# USB_Tool.net
KiCad netlist of a schematic drawn in Altium Designer
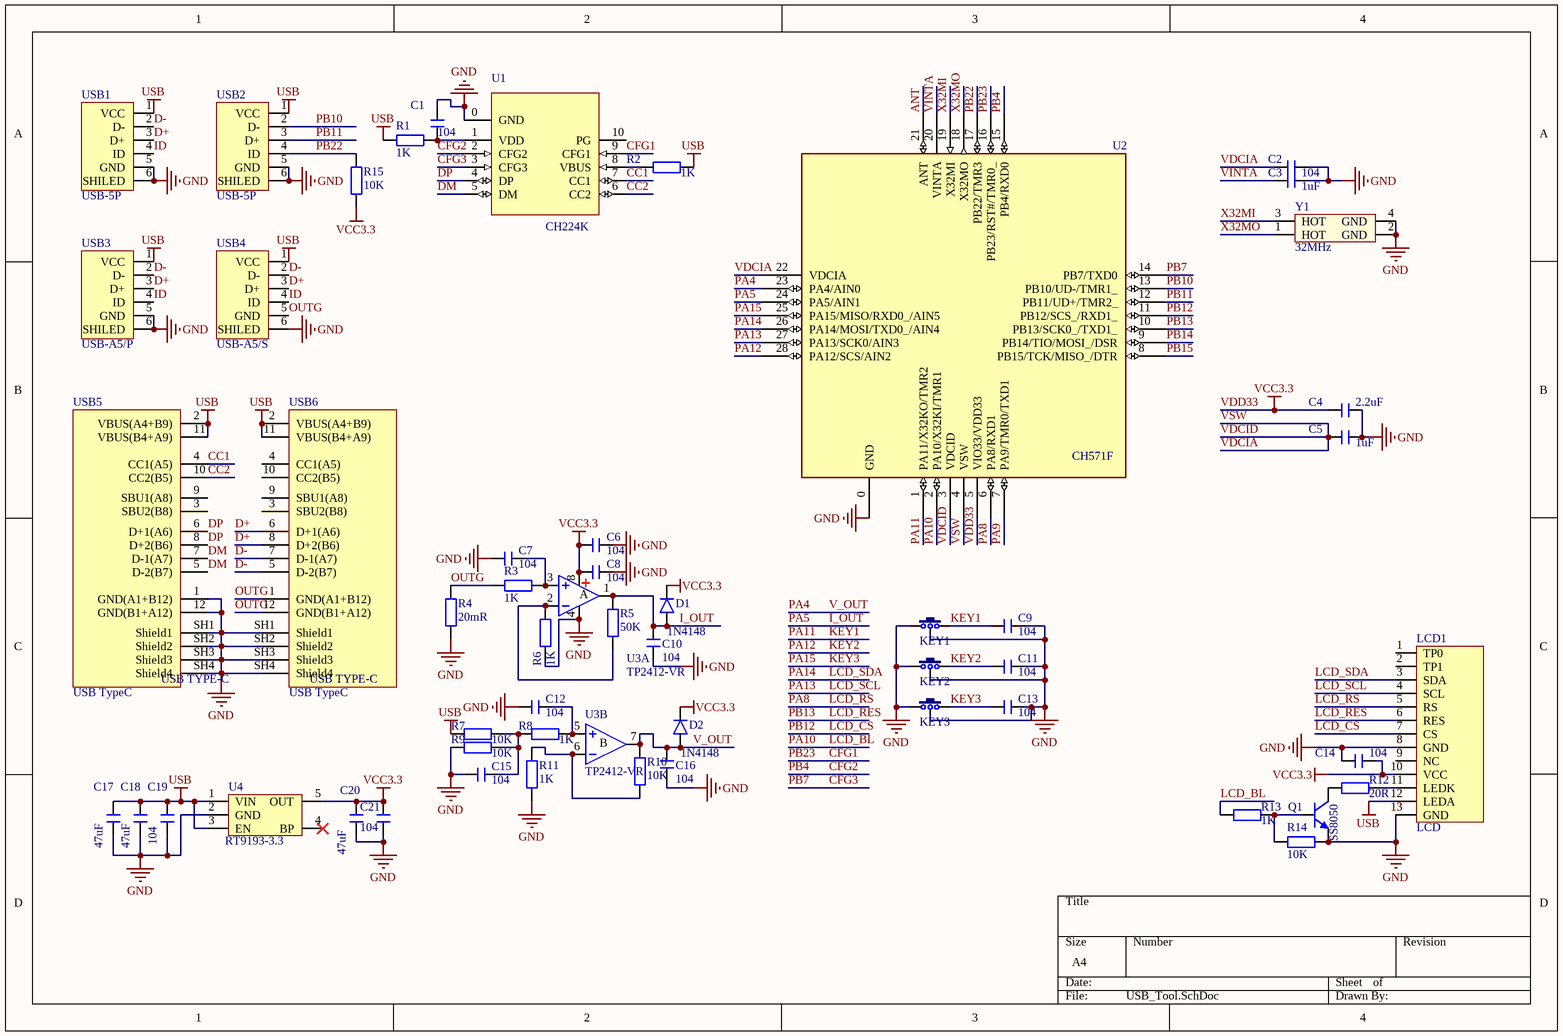
[diagram p0: USB_Tool.SchDoc]

(export (version "E")
  (design (tool "Eeschema 10.0.6"))
  (components
    (comp (ref "C1")
      (value "104")
      (footprint "C 0603_L")
      (description "无极性贴片电容")
      (fields (field (name "版权归属") "正点原子"))
      (libsource (lib "电阻-电容-电感") (part "C"))
    )
    (comp (ref "C2")
      (value "104")
      (footprint "C 0603_L")
      (description "无极性贴片电容")
      (libsource (lib "LovelessingSch") (part "C"))
    )
    (comp (ref "C3")
      (value "1uF")
      (footprint "C 0603_L")
      (description "无极性贴片电容")
      (libsource (lib "LovelessingSch") (part "C"))
    )
    (comp (ref "C4")
      (value "2.2uF")
      (footprint "C 0603_L")
      (description "无极性贴片电容")
      (libsource (lib "LovelessingSch") (part "C"))
    )
    (comp (ref "C5")
      (value "1uF")
      (footprint "C 0603_L")
      (description "无极性贴片电容")
      (libsource (lib "LovelessingSch") (part "C"))
    )
    (comp (ref "C6")
      (value "104")
      (footprint "C 0603_L")
      (description "无极性贴片电容")
      (fields (field (name "版权归属") "正点原子"))
      (libsource (lib "电阻-电容-电感") (part "C"))
    )
    (comp (ref "C7")
      (value "104")
      (footprint "C 0603_L")
      (description "无极性贴片电容")
      (fields (field (name "版权归属") "正点原子"))
      (libsource (lib "电阻-电容-电感") (part "C"))
    )
    (comp (ref "C8")
      (value "104")
      (footprint "C 0603_L")
      (description "无极性贴片电容")
      (fields (field (name "版权归属") "正点原子"))
      (libsource (lib "电阻-电容-电感") (part "C"))
    )
    (comp (ref "C9")
      (value "104")
      (footprint "C 0603_L")
      (description "无极性贴片电容")
      (fields (field (name "版权归属") "正点原子"))
      (libsource (lib "电阻-电容-电感") (part "C"))
    )
    (comp (ref "C10")
      (value "104")
      (footprint "C 0603_L")
      (description "无极性贴片电容")
      (fields (field (name "版权归属") "正点原子"))
      (libsource (lib "电阻-电容-电感") (part "C"))
    )
    (comp (ref "C11")
      (value "104")
      (footprint "C 0603_L")
      (description "无极性贴片电容")
      (fields (field (name "版权归属") "正点原子"))
      (libsource (lib "电阻-电容-电感") (part "C"))
    )
    (comp (ref "C12")
      (value "104")
      (footprint "C 0603_L")
      (description "无极性贴片电容")
      (fields (field (name "版权归属") "正点原子"))
      (libsource (lib "电阻-电容-电感") (part "C"))
    )
    (comp (ref "C13")
      (value "104")
      (footprint "C 0603_L")
      (description "无极性贴片电容")
      (fields (field (name "版权归属") "正点原子"))
      (libsource (lib "电阻-电容-电感") (part "C"))
    )
    (comp (ref "C14")
      (value "104")
      (footprint "C 0603_L")
      (description "无极性电容")
      (fields (field (name "版权归属") "正点原子"))
      (libsource (lib "正点原子封装库V1.0") (part "C"))
    )
    (comp (ref "C15")
      (value "104")
      (footprint "C 0603_L")
      (description "无极性贴片电容")
      (fields (field (name "版权归属") "正点原子"))
      (libsource (lib "电阻-电容-电感") (part "C"))
    )
    (comp (ref "C16")
      (value "104")
      (footprint "C 0603_L")
      (description "无极性贴片电容")
      (fields (field (name "版权归属") "正点原子"))
      (libsource (lib "电阻-电容-电感") (part "C"))
    )
    (comp (ref "C17")
      (value "47uF")
      (footprint "C 0603_L")
      (description "无极性贴片电容")
      (fields (field (name "版权归属") "正点原子"))
      (libsource (lib "电阻-电容-电感") (part "C"))
    )
    (comp (ref "C18")
      (value "47uF")
      (footprint "C 0603_L")
      (description "无极性贴片电容")
      (fields (field (name "版权归属") "正点原子"))
      (libsource (lib "电阻-电容-电感") (part "C"))
    )
    (comp (ref "C19")
      (value "104")
      (footprint "C 0603_L")
      (description "无极性贴片电容")
      (fields (field (name "版权归属") "正点原子"))
      (libsource (lib "电阻-电容-电感") (part "C"))
    )
    (comp (ref "C20")
      (value "47uF")
      (footprint "C 0603_L")
      (description "无极性贴片电容")
      (fields (field (name "版权归属") "正点原子"))
      (libsource (lib "电阻-电容-电感") (part "C"))
    )
    (comp (ref "C21")
      (value "104")
      (footprint "C 0603_L")
      (description "无极性贴片电容")
      (fields (field (name "版权归属") "正点原子"))
      (libsource (lib "电阻-电容-电感") (part "C"))
    )
    (comp (ref "D1")
      (value "1N4148")
      (footprint "SOD-323")
      (description "二极管")
      (libsource (lib "LovelessingSch") (part "D"))
    )
    (comp (ref "D2")
      (value "1N4148")
      (footprint "SOD-323")
      (description "二极管")
      (libsource (lib "LovelessingSch") (part "D"))
    )
    (comp (ref "KEY1")
      (value "KEY_3")
      (footprint "TSW 2*4*3.5-S-W")
      (description "侧按键")
      (fields (field (name "版权归属") "正点原子"))
      (libsource (lib "正点原子封装库V1.0") (part "KEY_3"))
    )
    (comp (ref "KEY2")
      (value "KEY_3")
      (footprint "TSW 2*4*3.5-S-W")
      (description "侧按键")
      (fields (field (name "版权归属") "正点原子"))
      (libsource (lib "正点原子封装库V1.0") (part "KEY_3"))
    )
    (comp (ref "KEY3")
      (value "KEY_3")
      (footprint "TSW 2*4*3.5-S-W")
      (description "侧按键")
      (fields (field (name "版权归属") "正点原子"))
      (libsource (lib "正点原子封装库V1.0") (part "KEY_3"))
    )
    (comp (ref "LCD1")
      (value "LCD")
      (footprint "0.96LCD")
      (description "0.96 LCD 80*160")
      (fields (field (name "版权归属") "正点原子"))
      (libsource (lib "正点原子封装库V1.0") (part "LCD 0.96"))
    )
    (comp (ref "Q1")
      (value "SS8050")
      (footprint "SOT23-3N")
      (description "高频放大-NPN型")
      (fields (field (name "版权归属") "正点原子"))
      (libsource (lib "正点原子封装库V1.0") (part "8050-SMD"))
    )
    (comp (ref "R1")
      (value "1K")
      (footprint "R 0603_L")
      (description "贴片电阻")
      (libsource (lib "LovelessingSch") (part "R"))
    )
    (comp (ref "R2")
      (value "1K")
      (footprint "R 0603_L")
      (description "贴片电阻")
      (libsource (lib "LovelessingSch") (part "R"))
    )
    (comp (ref "R3")
      (value "1K")
      (footprint "R 0603_L")
      (description "贴片电阻")
      (libsource (lib "LovelessingSch") (part "R"))
    )
    (comp (ref "R4")
      (value "20mR")
      (footprint "R 2512_L")
      (description "贴片电阻")
      (libsource (lib "LovelessingSch") (part "R"))
    )
    (comp (ref "R5")
      (value "50K")
      (footprint "R 0603_L")
      (description "贴片电阻")
      (libsource (lib "LovelessingSch") (part "R"))
    )
    (comp (ref "R6")
      (value "1K")
      (footprint "R 0603_L")
      (description "贴片电阻")
      (libsource (lib "LovelessingSch") (part "R"))
    )
    (comp (ref "R7")
      (value "10K")
      (footprint "R 0603_L")
      (description "贴片电阻")
      (libsource (lib "LovelessingSch") (part "R"))
    )
    (comp (ref "R8")
      (value "1K")
      (footprint "R 0603_L")
      (description "贴片电阻")
      (libsource (lib "LovelessingSch") (part "R"))
    )
    (comp (ref "R9")
      (value "10K")
      (footprint "R 0603_L")
      (description "贴片电阻")
      (libsource (lib "LovelessingSch") (part "R"))
    )
    (comp (ref "R10")
      (value "10K")
      (footprint "R 0603_L")
      (description "贴片电阻")
      (libsource (lib "LovelessingSch") (part "R"))
    )
    (comp (ref "R11")
      (value "1K")
      (footprint "R 0603_L")
      (description "贴片电阻")
      (libsource (lib "LovelessingSch") (part "R"))
    )
    (comp (ref "R12")
      (value "20R")
      (footprint "R 0603_L")
      (description "贴片电阻")
      (libsource (lib "LovelessingSch") (part "R"))
    )
    (comp (ref "R13")
      (value "1K")
      (footprint "R 0603_L")
      (description "贴片电阻")
      (libsource (lib "LovelessingSch") (part "R"))
    )
    (comp (ref "R14")
      (value "10K")
      (footprint "R 0603_L")
      (description "贴片电阻")
      (libsource (lib "LovelessingSch") (part "R"))
    )
    (comp (ref "R15")
      (value "10K")
      (footprint "R 0603_L")
      (description "贴片电阻")
      (libsource (lib "LovelessingSch") (part "R"))
    )
    (comp (ref "U1")
      (value "CH224K")
      (footprint "ESSOP10")
      (description "USB PD & Type-C & Fast Charge Power Consumer Controller")
      (libsource (lib "CHXXX") (part "CH224K"))
    )
    (comp (ref "U2")
      (value "CH571F")
      (footprint "QFN28_4X4")
      (description "RISC-V MCU with BLE/USB/ADC/SPI/2*UART")
      (libsource (lib "LovelessingSch") (part "CH571F"))
    )
    (comp (ref "U3")
      (value "TP2412-VR")
      (footprint "SOP8_N")
      (description "低噪双路运放 5.5V 10MHz 1mV")
      (fields (field (name "版权归属") "正点原子"))
      (libsource (lib "正点原子封装库V1.0") (part "TP2412"))
    )
    (comp (ref "U4")
      (value "RT9193-3.3")
      (footprint "SOT23-5L")
      (description "LDO")
      (fields (field (name "版权归属") "正点原子"))
      (libsource (lib "LDO和DCDC") (part "LDO RT9193"))
    )
    (comp (ref "USB1")
      (value "USB-5P")
      (footprint "USB-micro_B")
      (description "micro_USB母座")
      (fields (field (name "版权归属") "正点原子"))
      (libsource (lib "正点原子封装库V1.0") (part "USB 2.0 micro B"))
    )
    (comp (ref "USB2")
      (value "USB-5P")
      (footprint "USB-micro_B")
      (description "micro_USB母座")
      (fields (field (name "版权归属") "正点原子"))
      (libsource (lib "正点原子封装库V1.0") (part "USB 2.0 micro B"))
    )
    (comp (ref "USB3")
      (value "USB-A5/P")
      (footprint "USB_A5/P_B")
      (description "micro_USB母座")
      (fields (field (name "版权归属") "正点原子"))
      (libsource (lib "正点原子封装库V1.0") (part "USB 2.0 micro B"))
    )
    (comp (ref "USB4")
      (value "USB-A5/S")
      (footprint "USB_A5/S_B")
      (description "micro_USB母座")
      (fields (field (name "版权归属") "正点原子"))
      (libsource (lib "正点原子封装库V1.0") (part "USB 2.0 micro B"))
    )
    (comp (ref "USB5")
      (value "USB TypeC")
      (footprint "USB Type-C")
      (description "12P TypeC 母座")
      (fields (field (name "版权归属") "正点原子"))
      (libsource (lib "") (part "USB 2.0 Type C_1"))
    )
    (comp (ref "USB6")
      (value "USB TypeC")
      (footprint "USB Type-C")
      (description "12P TypeC 母座")
      (fields (field (name "版权归属") "正点原子"))
      (libsource (lib "正点原子封装库V1.0") (part "USB 2.0 Type C"))
    )
    (comp (ref "Y1")
      (value "32MHz")
      (footprint "OSC 3225-4P")
      (description "晶振25MHz")
      (fields (field (name "PUBLISHER") "Altium Limited"))
      (libsource (lib "LovelessingSch") (part "Y-3225-4P"))
    )
  )
  (nets
    (net (code "1") (name "/ANT") (class "Default")
      (node (ref "U2") (pin "21") (pinfunction "ANT_21") (pintype "bidirectional"))
    )
    (net (code "2") (name "/CC1") (class "Default")
      (node (ref "U1") (pin "7") (pinfunction "CC1_7") (pintype "bidirectional"))
      (node (ref "USB5") (pin "4") (pinfunction "CC1(A5)_4") (pintype "passive"))
    )
    (net (code "3") (name "/CC2") (class "Default")
      (node (ref "U1") (pin "6") (pinfunction "CC2_6") (pintype "bidirectional"))
      (node (ref "USB5") (pin "10") (pinfunction "CC2(B5)_10") (pintype "passive"))
    )
    (net (code "4") (name "/CFG1") (class "Default")
      (node (ref "U1") (pin "9") (pinfunction "CFG1_9") (pintype "input"))
      (node (ref "U2") (pin "16") (pinfunction "PB23/RST#/TMR0__16") (pintype "bidirectional"))
    )
    (net (code "5") (name "/CFG2") (class "Default")
      (node (ref "U1") (pin "2") (pinfunction "CFG2_2") (pintype "input"))
      (node (ref "U2") (pin "15") (pinfunction "PB4/RXD0_15") (pintype "bidirectional"))
    )
    (net (code "6") (name "/CFG3") (class "Default")
      (node (ref "U1") (pin "3") (pinfunction "CFG3_3") (pintype "input"))
      (node (ref "U2") (pin "14") (pinfunction "PB7/TXD0_14") (pintype "bidirectional"))
    )
    (net (code "7") (name "/D+") (class "Default")
      (node (ref "USB1") (pin "3") (pinfunction "D+_3") (pintype "passive"))
      (node (ref "USB3") (pin "3") (pinfunction "D+_3") (pintype "passive"))
      (node (ref "USB4") (pin "3") (pinfunction "D+_3") (pintype "passive"))
      (node (ref "USB6") (pin "6") (pinfunction "D+1(A6)_6") (pintype "passive"))
      (node (ref "USB6") (pin "8") (pinfunction "D+2(B6)_8") (pintype "passive"))
    )
    (net (code "8") (name "/D-") (class "Default")
      (node (ref "USB1") (pin "2") (pinfunction "D-_2") (pintype "passive"))
      (node (ref "USB3") (pin "2") (pinfunction "D-_2") (pintype "passive"))
      (node (ref "USB4") (pin "2") (pinfunction "D-_2") (pintype "passive"))
      (node (ref "USB6") (pin "5") (pinfunction "D-2(B7)_5") (pintype "passive"))
      (node (ref "USB6") (pin "7") (pinfunction "D-1(A7)_7") (pintype "passive"))
    )
    (net (code "9") (name "/DM") (class "Default")
      (node (ref "U1") (pin "5") (pinfunction "DM_5") (pintype "bidirectional"))
      (node (ref "USB5") (pin "5") (pinfunction "D-2(B7)_5") (pintype "passive"))
      (node (ref "USB5") (pin "7") (pinfunction "D-1(A7)_7") (pintype "passive"))
    )
    (net (code "10") (name "/DP") (class "Default")
      (node (ref "U1") (pin "4") (pinfunction "DP_4") (pintype "bidirectional"))
      (node (ref "USB5") (pin "6") (pinfunction "D+1(A6)_6") (pintype "passive"))
      (node (ref "USB5") (pin "8") (pinfunction "D+2(B6)_8") (pintype "passive"))
    )
    (net (code "11") (name "/ID") (class "Default")
      (node (ref "USB1") (pin "4") (pinfunction "ID_4") (pintype "passive"))
      (node (ref "USB3") (pin "4") (pinfunction "ID_4") (pintype "passive"))
      (node (ref "USB4") (pin "4") (pinfunction "ID_4") (pintype "passive"))
    )
    (net (code "12") (name "/I_OUT") (class "Default")
      (node (ref "C10") (pin "2") (pinfunction "2_2") (pintype "passive"))
      (node (ref "D1") (pin "1") (pintype "passive"))
      (node (ref "R5") (pin "1") (pinfunction "1_1") (pintype "passive"))
      (node (ref "U2") (pin "24") (pinfunction "PA5/AIN1_24") (pintype "bidirectional"))
      (node (ref "U3") (pin "1") (pinfunction "OUT_1") (pintype "passive"))
    )
    (net (code "13") (name "/KEY1") (class "Default")
      (node (ref "C9") (pin "1") (pinfunction "1_1") (pintype "passive"))
      (node (ref "KEY1") (pin "2") (pinfunction "2_2") (pintype "passive"))
      (node (ref "U2") (pin "1") (pinfunction "PA11/X32KO/TMR2_1") (pintype "bidirectional"))
    )
    (net (code "14") (name "/KEY2") (class "Default")
      (node (ref "C11") (pin "1") (pinfunction "1_1") (pintype "passive"))
      (node (ref "KEY2") (pin "2") (pinfunction "2_2") (pintype "passive"))
      (node (ref "U2") (pin "28") (pinfunction "PA12/SCS/AIN2_28") (pintype "bidirectional"))
    )
    (net (code "15") (name "/KEY3") (class "Default")
      (node (ref "C13") (pin "1") (pinfunction "1_1") (pintype "passive"))
      (node (ref "KEY3") (pin "2") (pinfunction "2_2") (pintype "passive"))
      (node (ref "U2") (pin "25") (pinfunction "PA15/MISO/RXD0_/AIN5_25") (pintype "bidirectional"))
    )
    (net (code "16") (name "/LCD_BL") (class "Default")
      (node (ref "R13") (pin "1") (pinfunction "1_1") (pintype "passive"))
      (node (ref "U2") (pin "2") (pinfunction "PA10/X32KI/TMR1_2") (pintype "bidirectional"))
    )
    (net (code "17") (name "/LCD_CS") (class "Default")
      (node (ref "LCD1") (pin "7") (pinfunction "CS_7") (pintype "passive"))
      (node (ref "U2") (pin "11") (pinfunction "PB12/SCS_/RXD1__11") (pintype "bidirectional"))
    )
    (net (code "18") (name "/LCD_RES") (class "Default")
      (node (ref "LCD1") (pin "6") (pinfunction "RES_6") (pintype "passive"))
      (node (ref "U2") (pin "10") (pinfunction "PB13/SCK0_/TXD1__10") (pintype "bidirectional"))
    )
    (net (code "19") (name "/LCD_RS") (class "Default")
      (node (ref "LCD1") (pin "5") (pinfunction "RS_5") (pintype "passive"))
      (node (ref "U2") (pin "6") (pinfunction "PA8/RXD1_6") (pintype "bidirectional"))
    )
    (net (code "20") (name "/LCD_SCL") (class "Default")
      (node (ref "LCD1") (pin "4") (pinfunction "SCL_4") (pintype "passive"))
      (node (ref "U2") (pin "27") (pinfunction "PA13/SCK0/AIN3_27") (pintype "bidirectional"))
    )
    (net (code "21") (name "/LCD_SDA") (class "Default")
      (node (ref "LCD1") (pin "3") (pinfunction "SDA_3") (pintype "passive"))
      (node (ref "U2") (pin "26") (pinfunction "PA14/MOSI/TXD0_/AIN4_26") (pintype "bidirectional"))
    )
    (net (code "22") (name "/OUTG") (class "Default")
      (node (ref "R3") (pin "2") (pinfunction "2_2") (pintype "passive"))
      (node (ref "R4") (pin "2") (pinfunction "2_2") (pintype "passive"))
      (node (ref "USB4") (pin "5") (pinfunction "GND_5") (pintype "passive"))
      (node (ref "USB6") (pin "1") (pinfunction "GND(A1+B12)_1") (pintype "passive"))
      (node (ref "USB6") (pin "12") (pinfunction "GND(B1+A12)_12") (pintype "passive"))
    )
    (net (code "23") (name "/PA4") (class "Default")
      (node (ref "C16") (pin "2") (pinfunction "2_2") (pintype "passive"))
      (node (ref "D2") (pin "1") (pintype "passive"))
      (node (ref "R10") (pin "1") (pinfunction "1_1") (pintype "passive"))
      (node (ref "U2") (pin "23") (pinfunction "PA4/AIN0_23") (pintype "bidirectional"))
      (node (ref "U3") (pin "7") (pinfunction "OUT_7") (pintype "passive"))
    )
    (net (code "24") (name "/PA9") (class "Default")
      (node (ref "U2") (pin "7") (pinfunction "PA9/TMR0/TXD1_7") (pintype "bidirectional"))
    )
    (net (code "25") (name "/PB10") (class "Default")
      (node (ref "U2") (pin "13") (pinfunction "PB10/UD-/TMR1__13") (pintype "bidirectional"))
      (node (ref "USB2") (pin "2") (pinfunction "D-_2") (pintype "passive"))
    )
    (net (code "26") (name "/PB11") (class "Default")
      (node (ref "U2") (pin "12") (pinfunction "PB11/UD+/TMR2__12") (pintype "bidirectional"))
      (node (ref "USB2") (pin "3") (pinfunction "D+_3") (pintype "passive"))
    )
    (net (code "27") (name "/PB14") (class "Default")
      (node (ref "U2") (pin "9") (pinfunction "PB14/TIO/MOSI_/DSR_9") (pintype "bidirectional"))
    )
    (net (code "28") (name "/PB15") (class "Default")
      (node (ref "U2") (pin "8") (pinfunction "PB15/TCK/MISO_/DTR_8") (pintype "bidirectional"))
    )
    (net (code "29") (name "/PB22") (class "Default")
      (node (ref "R15") (pin "1") (pinfunction "1_1") (pintype "passive"))
      (node (ref "U2") (pin "17") (pinfunction "PB22/TMR3_17") (pintype "bidirectional"))
      (node (ref "USB2") (pin "4") (pinfunction "ID_4") (pintype "passive"))
    )
    (net (code "30") (name "/VDCIA") (class "Default")
      (node (ref "C2") (pin "1") (pinfunction "1_1") (pintype "passive"))
      (node (ref "C5") (pin "1") (pinfunction "1_1") (pintype "passive"))
      (node (ref "U2") (pin "22") (pinfunction "VDCIA_22") (pintype "power_in"))
      (node (ref "U2") (pin "3") (pinfunction "VDCID_3") (pintype "power_in"))
      (node (ref "U2") (pin "4") (pinfunction "VSW_4") (pintype "power_in"))
    )
    (net (code "31") (name "/VINTA") (class "Default")
      (node (ref "C3") (pin "1") (pinfunction "1_1") (pintype "passive"))
      (node (ref "U2") (pin "20") (pinfunction "VINTA_20") (pintype "power_in"))
    )
    (net (code "32") (name "/X32MI") (class "Default")
      (node (ref "U2") (pin "19") (pinfunction "X32MI_19") (pintype "input"))
      (node (ref "Y1") (pin "3") (pinfunction "HOT_3") (pintype "passive"))
    )
    (net (code "33") (name "/X32MO") (class "Default")
      (node (ref "U2") (pin "18") (pinfunction "X32MO_18") (pintype "output"))
      (node (ref "Y1") (pin "1") (pinfunction "HOT_1") (pintype "passive"))
    )
    (net (code "34") (name "GND") (class "Default")
      (node (ref "C1") (pin "1") (pinfunction "1_1") (pintype "passive"))
      (node (ref "C10") (pin "1") (pinfunction "1_1") (pintype "passive"))
      (node (ref "C11") (pin "2") (pinfunction "2_2") (pintype "passive"))
      (node (ref "C12") (pin "2") (pinfunction "2_2") (pintype "passive"))
      (node (ref "C13") (pin "2") (pinfunction "2_2") (pintype "passive"))
      (node (ref "C14") (pin "2") (pinfunction "2_2") (pintype "passive"))
      (node (ref "C15") (pin "2") (pinfunction "2_2") (pintype "passive"))
      (node (ref "C16") (pin "1") (pinfunction "1_1") (pintype "passive"))
      (node (ref "C17") (pin "2") (pinfunction "2_2") (pintype "passive"))
      (node (ref "C18") (pin "2") (pinfunction "2_2") (pintype "passive"))
      (node (ref "C19") (pin "2") (pinfunction "2_2") (pintype "passive"))
      (node (ref "C2") (pin "2") (pinfunction "2_2") (pintype "passive"))
      (node (ref "C20") (pin "2") (pinfunction "2_2") (pintype "passive"))
      (node (ref "C21") (pin "2") (pinfunction "2_2") (pintype "passive"))
      (node (ref "C3") (pin "2") (pinfunction "2_2") (pintype "passive"))
      (node (ref "C4") (pin "2") (pinfunction "2_2") (pintype "passive"))
      (node (ref "C5") (pin "2") (pinfunction "2_2") (pintype "passive"))
      (node (ref "C6") (pin "2") (pinfunction "2_2") (pintype "passive"))
      (node (ref "C7") (pin "2") (pinfunction "2_2") (pintype "passive"))
      (node (ref "C8") (pin "2") (pinfunction "2_2") (pintype "passive"))
      (node (ref "C9") (pin "2") (pinfunction "2_2") (pintype "passive"))
      (node (ref "KEY1") (pin "0") (pinfunction "0_0") (pintype "passive"))
      (node (ref "KEY1") (pin "1") (pinfunction "1_1") (pintype "passive"))
      (node (ref "KEY2") (pin "0") (pinfunction "0_0") (pintype "passive"))
      (node (ref "KEY2") (pin "1") (pinfunction "1_1") (pintype "passive"))
      (node (ref "KEY3") (pin "0") (pinfunction "0_0") (pintype "passive"))
      (node (ref "KEY3") (pin "1") (pinfunction "1_1") (pintype "passive"))
      (node (ref "LCD1") (pin "13") (pinfunction "GND_13") (pintype "passive"))
      (node (ref "LCD1") (pin "8") (pinfunction "GND_8") (pintype "passive"))
      (node (ref "Q1") (pin "2") (pinfunction "E_2") (pintype "passive"))
      (node (ref "R11") (pin "2") (pinfunction "2_2") (pintype "passive"))
      (node (ref "R14") (pin "2") (pinfunction "2_2") (pintype "passive"))
      (node (ref "R4") (pin "1") (pinfunction "1_1") (pintype "passive"))
      (node (ref "R6") (pin "1") (pinfunction "1_1") (pintype "passive"))
      (node (ref "R9") (pin "2") (pinfunction "2_2") (pintype "passive"))
      (node (ref "U1") (pin "0") (pinfunction "GND_0") (pintype "power_in"))
      (node (ref "U2") (pin "0") (pinfunction "GND_0") (pintype "power_in"))
      (node (ref "U3") (pin "4") (pinfunction "V-_4") (pintype "passive"))
      (node (ref "U4") (pin "2") (pinfunction "GND_2") (pintype "passive"))
      (node (ref "USB1") (pin "5") (pinfunction "GND_5") (pintype "passive"))
      (node (ref "USB1") (pin "6") (pinfunction "SHILED_6") (pintype "passive"))
      (node (ref "USB2") (pin "5") (pinfunction "GND_5") (pintype "passive"))
      (node (ref "USB2") (pin "6") (pinfunction "SHILED_6") (pintype "passive"))
      (node (ref "USB3") (pin "5") (pinfunction "GND_5") (pintype "passive"))
      (node (ref "USB3") (pin "6") (pinfunction "SHILED_6") (pintype "passive"))
      (node (ref "USB4") (pin "6") (pinfunction "SHILED_6") (pintype "passive"))
      (node (ref "USB5") (pin "1") (pinfunction "GND(A1+B12)_1") (pintype "passive"))
      (node (ref "USB5") (pin "12") (pinfunction "GND(B1+A12)_12") (pintype "passive"))
      (node (ref "USB5") (pin "SH1") (pinfunction "Shield1_SH1") (pintype "passive"))
      (node (ref "USB5") (pin "SH2") (pinfunction "Shield2_SH2") (pintype "passive"))
      (node (ref "USB5") (pin "SH3") (pinfunction "Shield3_SH3") (pintype "passive"))
      (node (ref "USB5") (pin "SH4") (pinfunction "Shield4_SH4") (pintype "passive"))
      (node (ref "USB6") (pin "SH1") (pinfunction "Shield1_SH1") (pintype "passive"))
      (node (ref "USB6") (pin "SH2") (pinfunction "Shield2_SH2") (pintype "passive"))
      (node (ref "USB6") (pin "SH3") (pinfunction "Shield3_SH3") (pintype "passive"))
      (node (ref "USB6") (pin "SH4") (pinfunction "Shield4_SH4") (pintype "passive"))
      (node (ref "Y1") (pin "2") (pinfunction "GND_2") (pintype "passive"))
      (node (ref "Y1") (pin "4") (pinfunction "GND_4") (pintype "passive"))
    )
    (net (code "35") (name "Net-(C15-Pad1)") (class "Default")
      (node (ref "C15") (pin "1") (pinfunction "1_1") (pintype "passive"))
      (node (ref "R7") (pin "1") (pinfunction "1_1") (pintype "passive"))
      (node (ref "R8") (pin "2") (pinfunction "2_2") (pintype "passive"))
      (node (ref "R9") (pin "1") (pinfunction "1_1") (pintype "passive"))
    )
    (net (code "36") (name "Net-(LCD1-LEDK)") (class "Default")
      (node (ref "LCD1") (pin "11") (pinfunction "LEDK_11") (pintype "passive"))
      (node (ref "R12") (pin "2") (pinfunction "2_2") (pintype "passive"))
    )
    (net (code "37") (name "Net-(Q1-B)") (class "Default")
      (node (ref "Q1") (pin "1") (pinfunction "B_1") (pintype "passive"))
      (node (ref "R13") (pin "2") (pinfunction "2_2") (pintype "passive"))
      (node (ref "R14") (pin "1") (pinfunction "1_1") (pintype "passive"))
    )
    (net (code "38") (name "Net-(Q1-C)") (class "Default")
      (node (ref "Q1") (pin "3") (pinfunction "C_3") (pintype "passive"))
      (node (ref "R12") (pin "1") (pinfunction "1_1") (pintype "passive"))
    )
    (net (code "39") (name "Net-(U1-VBUS)") (class "Default")
      (node (ref "R2") (pin "1") (pinfunction "1_1") (pintype "passive"))
      (node (ref "U1") (pin "8") (pinfunction "VBUS_8") (pintype "input"))
    )
    (net (code "40") (name "Net-(U1-VDD)") (class "Default")
      (node (ref "C1") (pin "2") (pinfunction "2_2") (pintype "passive"))
      (node (ref "R1") (pin "1") (pinfunction "1_1") (pintype "passive"))
      (node (ref "U1") (pin "1") (pinfunction "VDD_1") (pintype "power_in"))
    )
    (net (code "41") (name "Net-(U3A-IN+)") (class "Default")
      (node (ref "C7") (pin "1") (pinfunction "1_1") (pintype "passive"))
      (node (ref "R3") (pin "1") (pinfunction "1_1") (pintype "passive"))
      (node (ref "U3") (pin "3") (pinfunction "IN+_3") (pintype "passive"))
    )
    (net (code "42") (name "Net-(U3A-IN-)") (class "Default")
      (node (ref "R5") (pin "2") (pinfunction "2_2") (pintype "passive"))
      (node (ref "R6") (pin "2") (pinfunction "2_2") (pintype "passive"))
      (node (ref "U3") (pin "2") (pinfunction "IN-_2") (pintype "passive"))
    )
    (net (code "43") (name "Net-(U3B-IN+)") (class "Default")
      (node (ref "C12") (pin "1") (pinfunction "1_1") (pintype "passive"))
      (node (ref "R8") (pin "1") (pinfunction "1_1") (pintype "passive"))
      (node (ref "U3") (pin "5") (pinfunction "IN+_5") (pintype "passive"))
    )
    (net (code "44") (name "Net-(U3B-IN-)") (class "Default")
      (node (ref "R10") (pin "2") (pinfunction "2_2") (pintype "passive"))
      (node (ref "R11") (pin "1") (pinfunction "1_1") (pintype "passive"))
      (node (ref "U3") (pin "6") (pinfunction "IN-_6") (pintype "passive"))
    )
    (net (code "45") (name "USB") (class "Default")
      (node (ref "C17") (pin "1") (pinfunction "1_1") (pintype "passive"))
      (node (ref "C18") (pin "1") (pinfunction "1_1") (pintype "passive"))
      (node (ref "C19") (pin "1") (pinfunction "1_1") (pintype "passive"))
      (node (ref "LCD1") (pin "12") (pinfunction "LEDA_12") (pintype "passive"))
      (node (ref "R1") (pin "2") (pinfunction "2_2") (pintype "passive"))
      (node (ref "R2") (pin "2") (pinfunction "2_2") (pintype "passive"))
      (node (ref "R7") (pin "2") (pinfunction "2_2") (pintype "passive"))
      (node (ref "U4") (pin "1") (pinfunction "VIN_1") (pintype "passive"))
      (node (ref "U4") (pin "3") (pinfunction "EN_3") (pintype "passive"))
      (node (ref "USB1") (pin "1") (pinfunction "VCC_1") (pintype "passive"))
      (node (ref "USB2") (pin "1") (pinfunction "VCC_1") (pintype "passive"))
      (node (ref "USB3") (pin "1") (pinfunction "VCC_1") (pintype "passive"))
      (node (ref "USB4") (pin "1") (pinfunction "VCC_1") (pintype "passive"))
      (node (ref "USB5") (pin "11") (pinfunction "VBUS(B4+A9)_11") (pintype "passive"))
      (node (ref "USB5") (pin "2") (pinfunction "VBUS(A4+B9)_2") (pintype "passive"))
      (node (ref "USB6") (pin "11") (pinfunction "VBUS(B4+A9)_11") (pintype "passive"))
      (node (ref "USB6") (pin "2") (pinfunction "VBUS(A4+B9)_2") (pintype "passive"))
    )
    (net (code "46") (name "VCC3.3") (class "Default")
      (node (ref "C14") (pin "1") (pinfunction "1_1") (pintype "passive"))
      (node (ref "C20") (pin "1") (pinfunction "1_1") (pintype "passive"))
      (node (ref "C21") (pin "1") (pinfunction "1_1") (pintype "passive"))
      (node (ref "C4") (pin "1") (pinfunction "1_1") (pintype "passive"))
      (node (ref "C6") (pin "1") (pinfunction "1_1") (pintype "passive"))
      (node (ref "C8") (pin "1") (pinfunction "1_1") (pintype "passive"))
      (node (ref "D1") (pin "2") (pintype "passive"))
      (node (ref "D2") (pin "2") (pintype "passive"))
      (node (ref "LCD1") (pin "10") (pinfunction "VCC_10") (pintype "passive"))
      (node (ref "R15") (pin "2") (pinfunction "2_2") (pintype "passive"))
      (node (ref "U2") (pin "5") (pinfunction "VIO33/VDD33_5") (pintype "power_in"))
      (node (ref "U3") (pin "8") (pinfunction "V+_8") (pintype "passive"))
      (node (ref "U4") (pin "5") (pinfunction "OUT_5") (pintype "passive"))
    )
    (net (code "47") (name "unconnected-(LCD1-NC-Pad9)") (class "Default")
      (node (ref "LCD1") (pin "9") (pinfunction "NC_9") (pintype "passive"))
    )
    (net (code "48") (name "unconnected-(LCD1-TP0-Pad1)") (class "Default")
      (node (ref "LCD1") (pin "1") (pinfunction "TP0_1") (pintype "passive"))
    )
    (net (code "49") (name "unconnected-(LCD1-TP1-Pad2)") (class "Default")
      (node (ref "LCD1") (pin "2") (pinfunction "TP1_2") (pintype "passive"))
    )
    (net (code "50") (name "unconnected-(U1-PG-Pad10)") (class "Default")
      (node (ref "U1") (pin "10") (pinfunction "PG_10") (pintype "passive"))
    )
    (net (code "51") (name "unconnected-(U4-BP-Pad4)") (class "Default")
      (node (ref "U4") (pin "4") (pinfunction "BP_4") (pintype "passive+no_connect"))
    )
    (net (code "52") (name "unconnected-(USB5-SBU1(A8)-Pad9)") (class "Default")
      (node (ref "USB5") (pin "9") (pinfunction "SBU1(A8)_9") (pintype "passive"))
    )
    (net (code "53") (name "unconnected-(USB5-SBU2(B8)-Pad3)") (class "Default")
      (node (ref "USB5") (pin "3") (pinfunction "SBU2(B8)_3") (pintype "passive"))
    )
    (net (code "54") (name "unconnected-(USB6-CC1(A5)-Pad4)") (class "Default")
      (node (ref "USB6") (pin "4") (pinfunction "CC1(A5)_4") (pintype "passive"))
    )
    (net (code "55") (name "unconnected-(USB6-CC2(B5)-Pad10)") (class "Default")
      (node (ref "USB6") (pin "10") (pinfunction "CC2(B5)_10") (pintype "passive"))
    )
    (net (code "56") (name "unconnected-(USB6-SBU1(A8)-Pad9)") (class "Default")
      (node (ref "USB6") (pin "9") (pinfunction "SBU1(A8)_9") (pintype "passive"))
    )
    (net (code "57") (name "unconnected-(USB6-SBU2(B8)-Pad3)") (class "Default")
      (node (ref "USB6") (pin "3") (pinfunction "SBU2(B8)_3") (pintype "passive"))
    )
  )
)
